# proudovyzdroj.net
KiCad netlist of a schematic drawn in EAGLE
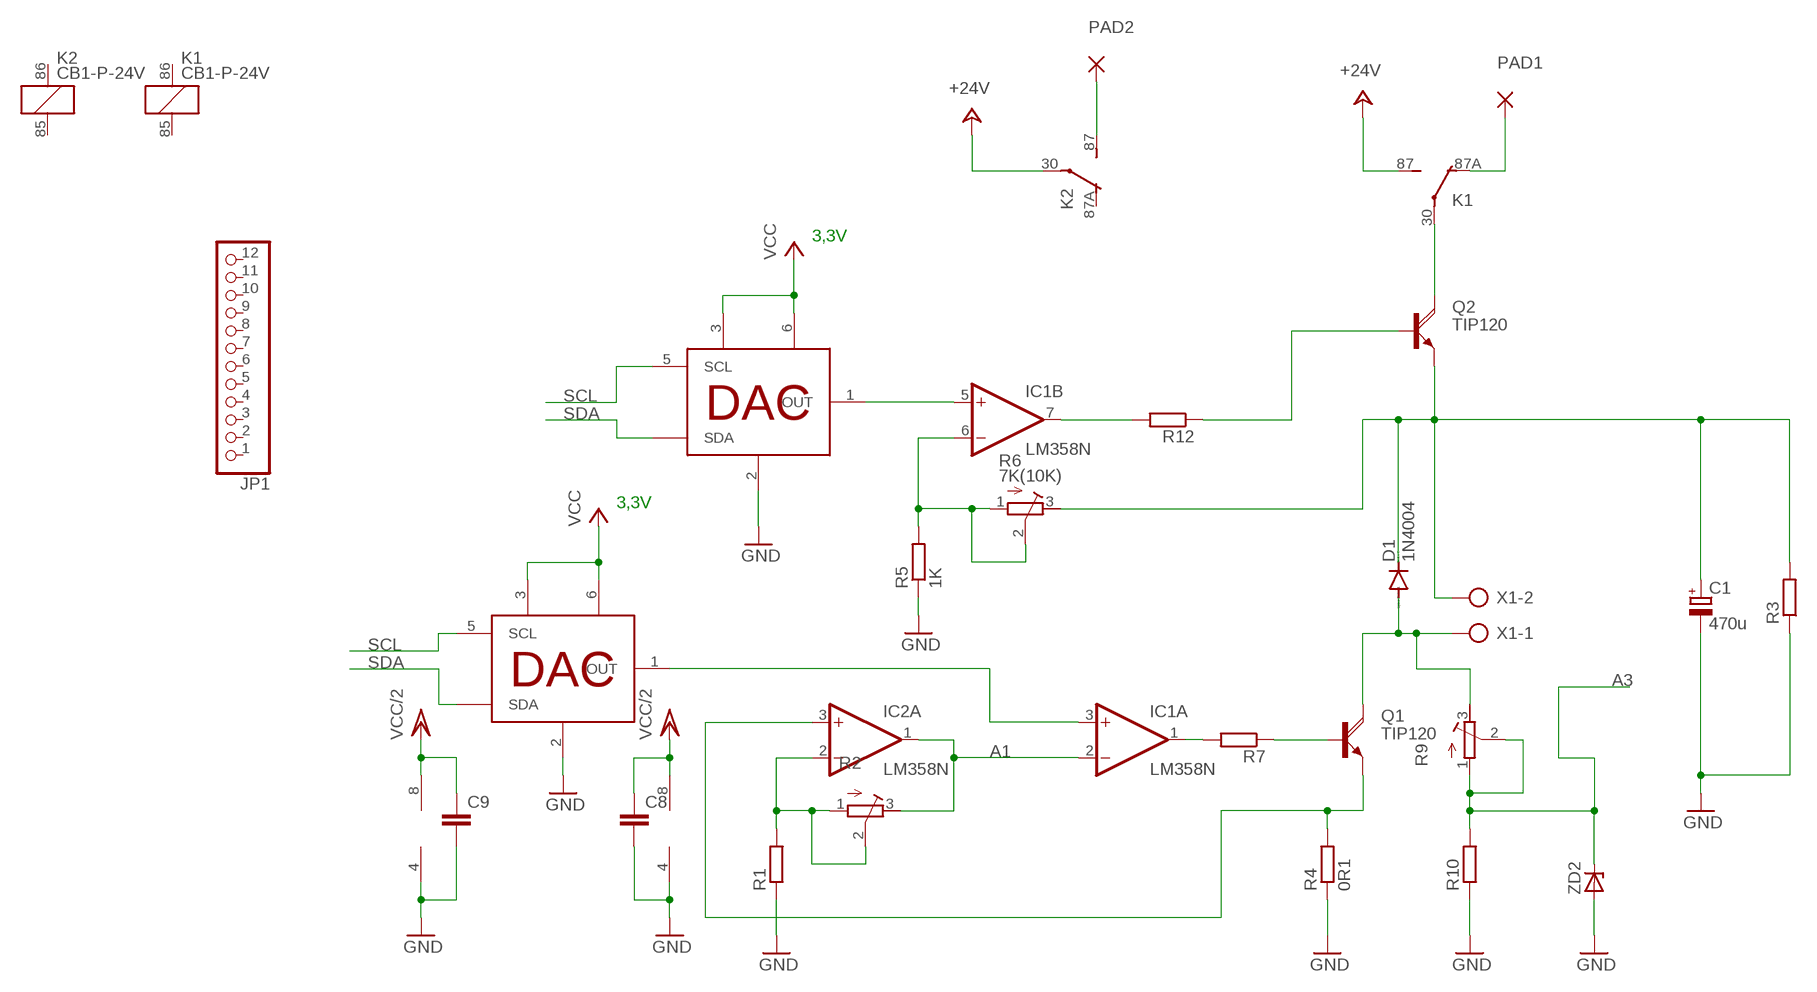
[diagram p0: schematic, sheet 1]

(export (version "E")
  (design (tool "Eeschema 10.0.6"))
  (components
    (comp (ref "C1")
      (value "470u")
      (footprint "eagle-import:E3,5-8")
      (libsource (lib "eagle-import") (part "CPOL-EUE3.5-8"))
    )
    (comp (ref "C8")
      (value "C-EUC0805")
      (footprint "eagle-import:C0805")
      (libsource (lib "eagle-import") (part "C-EUC0805"))
    )
    (comp (ref "C9")
      (value "C-EUC0805")
      (footprint "eagle-import:C0805")
      (libsource (lib "eagle-import") (part "C-EUC0805"))
    )
    (comp (ref "D1")
      (value "1N4004")
      (footprint "eagle-import:DO41-10")
      (libsource (lib "eagle-import") (part "1N4004"))
    )
    (comp (ref "IC1")
      (value "LM358N")
      (footprint "eagle-import:DIL08")
      (libsource (lib "eagle-import") (part "LM358N"))
    )
    (comp (ref "IC2")
      (value "LM358N")
      (footprint "eagle-import:DIL08")
      (libsource (lib "eagle-import") (part "LM358N"))
    )
    (comp (ref "JP1")
      (value "PINHD-1X12")
      (footprint "eagle-import:1X12")
      (libsource (lib "eagle-import") (part "PINHD-1X12"))
    )
    (comp (ref "K1")
      (value "CB1-P-24V")
      (footprint "eagle-import:CB1")
      (fields (field (name "MF") "AROMAT/ MATSUSHITA"))
      (libsource (lib "eagle-import") (part "CB1-P-24V"))
    )
    (comp (ref "K2")
      (value "CB1-P-24V")
      (footprint "eagle-import:CB1")
      (fields (field (name "MF") "AROMAT/ MATSUSHITA"))
      (libsource (lib "eagle-import") (part "CB1-P-24V"))
    )
    (comp (ref "PAD1")
      (value "3,81/1,4")
      (footprint "eagle-import:3,81_1,4")
      (libsource (lib "eagle-import") (part "3,81/1,4"))
    )
    (comp (ref "PAD2")
      (value "3,81/1,4")
      (footprint "eagle-import:3,81_1,4")
      (libsource (lib "eagle-import") (part "3,81/1,4"))
    )
    (comp (ref "Q1")
      (value "TIP120")
      (footprint "eagle-import:TO220AH")
      (libsource (lib "eagle-import") (part "TIP120"))
    )
    (comp (ref "Q2")
      (value "TIP120")
      (footprint "eagle-import:TO220AH")
      (libsource (lib "eagle-import") (part "TIP120"))
    )
    (comp (ref "R1")
      (value "R-EU_M0805")
      (footprint "eagle-import:M0805")
      (libsource (lib "eagle-import") (part "rcl_my_R-EU_M0805"))
    )
    (comp (ref "R2")
      (value "R-TRIMM3339P")
      (footprint "eagle-import:RTRIM3339P")
      (libsource (lib "eagle-import") (part "R-TRIMM3339P"))
    )
    (comp (ref "R3")
      (value "R-EU_R0805")
      (footprint "eagle-import:R0805")
      (libsource (lib "eagle-import") (part "R-EU_R0805"))
    )
    (comp (ref "R4")
      (value "0R1")
      (footprint "eagle-import:0411_15")
      (libsource (lib "eagle-import") (part "R-EU_0411/15"))
    )
    (comp (ref "R5")
      (value "1K")
      (footprint "eagle-import:R0805")
      (libsource (lib "eagle-import") (part "R-EU_R0805"))
    )
    (comp (ref "R6")
      (value "7K(10K)")
      (footprint "eagle-import:RTRIM3339P")
      (libsource (lib "eagle-import") (part "R-TRIMM3339P"))
    )
    (comp (ref "R7")
      (value "R-EU_R0805")
      (footprint "eagle-import:R0805")
      (libsource (lib "eagle-import") (part "R-EU_R0805"))
    )
    (comp (ref "R9")
      (value "R-TRIMM3339P")
      (footprint "eagle-import:RTRIM3339P")
      (libsource (lib "eagle-import") (part "R-TRIMM3339P"))
    )
    (comp (ref "R10")
      (value "R-EU_R0805")
      (footprint "eagle-import:R0805")
      (libsource (lib "eagle-import") (part "R-EU_R0805"))
    )
    (comp (ref "R12")
      (value "R-EU_R0805")
      (footprint "eagle-import:R0805")
      (libsource (lib "eagle-import") (part "R-EU_R0805"))
    )
    (comp (ref "U$5")
      (value "MCP4726")
      (footprint "eagle-import:TSOT23-6")
      (libsource (lib "eagle-import") (part "MCP4726"))
    )
    (comp (ref "U$6")
      (value "MCP4726")
      (footprint "eagle-import:TSOT23-6")
      (libsource (lib "eagle-import") (part "MCP4726"))
    )
    (comp (ref "X1")
      (value "AK500/2")
      (footprint "eagle-import:AK500_2")
      (libsource (lib "eagle-import") (part "AK500/2"))
    )
    (comp (ref "ZD2")
      (value "DIODE_ZENER5")
      (footprint "eagle-import:DO34-5")
      (libsource (lib "eagle-import") (part "DIODE_ZENER5"))
    )
  )
  (nets
    (net (code "1") (name "+24V") (class "Default")
      (node (ref "K1") (pin "87") (pinfunction "S_87") (pintype "passive"))
      (node (ref "K2") (pin "30") (pinfunction "P_30") (pintype "passive"))
    )
    (net (code "2") (name "/A1") (class "Default")
      (node (ref "IC1") (pin "2") (pinfunction "-IN_2") (pintype "input"))
      (node (ref "IC2") (pin "1") (pinfunction "OUT_1") (pintype "output"))
      (node (ref "R2") (pin "3") (pinfunction "E_3") (pintype "passive"))
    )
    (net (code "3") (name "/A3") (class "Default")
      (node (ref "R10") (pin "2") (pinfunction "2_2") (pintype "passive"))
      (node (ref "R9") (pin "1") (pinfunction "A_1") (pintype "passive"))
      (node (ref "R9") (pin "2") (pinfunction "S_2") (pintype "passive"))
      (node (ref "ZD2") (pin "C") (pinfunction "C_C") (pintype "passive"))
    )
    (net (code "4") (name "/SCL") (class "Default")
      (node (ref "U$5") (pin "5") (pinfunction "SCL_5") (pintype "bidirectional"))
      (node (ref "U$6") (pin "5") (pinfunction "SCL_5") (pintype "bidirectional"))
    )
    (net (code "5") (name "/SDA") (class "Default")
      (node (ref "U$5") (pin "4") (pinfunction "SDA_4") (pintype "bidirectional"))
      (node (ref "U$6") (pin "4") (pinfunction "SDA_4") (pintype "bidirectional"))
    )
    (net (code "6") (name "GND") (class "Default")
      (node (ref "C1") (pin "-") (pinfunction "-_-") (pintype "passive"))
      (node (ref "C8") (pin "2") (pinfunction "2_2") (pintype "passive"))
      (node (ref "C9") (pin "2") (pinfunction "2_2") (pintype "passive"))
      (node (ref "IC1") (pin "4") (pinfunction "V-_4") (pintype "power_in"))
      (node (ref "IC2") (pin "4") (pinfunction "V-_4") (pintype "power_in"))
      (node (ref "R1") (pin "1") (pinfunction "1_1") (pintype "passive"))
      (node (ref "R10") (pin "1") (pinfunction "1_1") (pintype "passive"))
      (node (ref "R3") (pin "1") (pinfunction "1_1") (pintype "passive"))
      (node (ref "R4") (pin "1") (pinfunction "1_1") (pintype "passive"))
      (node (ref "R5") (pin "1") (pinfunction "1_1") (pintype "passive"))
      (node (ref "U$5") (pin "2") (pinfunction "VSS_2") (pintype "bidirectional"))
      (node (ref "U$6") (pin "2") (pinfunction "VSS_2") (pintype "bidirectional"))
      (node (ref "ZD2") (pin "A") (pinfunction "A_A") (pintype "passive"))
    )
    (net (code "7") (name "Net-(IC1A-+IN)") (class "Default")
      (node (ref "IC1") (pin "3") (pinfunction "+IN_3") (pintype "input"))
      (node (ref "U$5") (pin "1") (pinfunction "OUT_1") (pintype "bidirectional"))
    )
    (net (code "8") (name "Net-(IC1A-OUT)") (class "Default")
      (node (ref "IC1") (pin "1") (pinfunction "OUT_1") (pintype "output"))
      (node (ref "R7") (pin "2") (pinfunction "2_2") (pintype "passive"))
    )
    (net (code "9") (name "Net-(IC1B-+IN)") (class "Default")
      (node (ref "IC1") (pin "5") (pinfunction "+IN_5") (pintype "input"))
      (node (ref "U$6") (pin "1") (pinfunction "OUT_1") (pintype "bidirectional"))
    )
    (net (code "10") (name "Net-(IC1B--IN)") (class "Default")
      (node (ref "IC1") (pin "6") (pinfunction "-IN_6") (pintype "input"))
      (node (ref "R5") (pin "2") (pinfunction "2_2") (pintype "passive"))
      (node (ref "R6") (pin "1") (pinfunction "A_1") (pintype "passive"))
      (node (ref "R6") (pin "2") (pinfunction "S_2") (pintype "passive"))
    )
    (net (code "11") (name "Net-(IC1B-OUT)") (class "Default")
      (node (ref "IC1") (pin "7") (pinfunction "OUT_7") (pintype "output"))
      (node (ref "R12") (pin "2") (pinfunction "2_2") (pintype "passive"))
    )
    (net (code "12") (name "Net-(IC2A-+IN)") (class "Default")
      (node (ref "IC2") (pin "3") (pinfunction "+IN_3") (pintype "input"))
      (node (ref "Q1") (pin "E") (pinfunction "E_E") (pintype "passive"))
      (node (ref "R4") (pin "2") (pinfunction "2_2") (pintype "passive"))
    )
    (net (code "13") (name "Net-(IC2A--IN)") (class "Default")
      (node (ref "IC2") (pin "2") (pinfunction "-IN_2") (pintype "input"))
      (node (ref "R1") (pin "2") (pinfunction "2_2") (pintype "passive"))
      (node (ref "R2") (pin "1") (pinfunction "A_1") (pintype "passive"))
      (node (ref "R2") (pin "2") (pinfunction "S_2") (pintype "passive"))
    )
    (net (code "14") (name "Net-(K1B-O)") (class "Default")
      (node (ref "K1") (pin "87A") (pinfunction "O_87A") (pintype "passive"))
      (node (ref "PAD1") (pin "1") (pinfunction "P_1") (pintype "passive"))
    )
    (net (code "15") (name "Net-(K1B-P)") (class "Default")
      (node (ref "K1") (pin "30") (pinfunction "P_30") (pintype "passive"))
      (node (ref "Q2") (pin "C") (pinfunction "C_C") (pintype "passive"))
    )
    (net (code "16") (name "Net-(K2B-S)") (class "Default")
      (node (ref "K2") (pin "87") (pinfunction "S_87") (pintype "passive"))
      (node (ref "PAD2") (pin "1") (pinfunction "P_1") (pintype "passive"))
    )
    (net (code "17") (name "Net-(Q1-PadB)") (class "Default")
      (node (ref "Q1") (pin "B") (pinfunction "B_B") (pintype "passive"))
      (node (ref "R7") (pin "1") (pinfunction "1_1") (pintype "passive"))
    )
    (net (code "18") (name "Net-(Q2-PadB)") (class "Default")
      (node (ref "Q2") (pin "B") (pinfunction "B_B") (pintype "passive"))
      (node (ref "R12") (pin "1") (pinfunction "1_1") (pintype "passive"))
    )
    (net (code "19") (name "Net-(R6-E)") (class "Default")
      (node (ref "C1") (pin "+") (pinfunction "+_+") (pintype "passive"))
      (node (ref "D1") (pin "C") (pinfunction "C_C") (pintype "passive"))
      (node (ref "Q2") (pin "E") (pinfunction "E_E") (pintype "passive"))
      (node (ref "R3") (pin "2") (pinfunction "2_2") (pintype "passive"))
      (node (ref "R6") (pin "3") (pinfunction "E_3") (pintype "passive"))
      (node (ref "X1") (pin "2") (pinfunction "KL_2") (pintype "passive"))
    )
    (net (code "20") (name "Net-(R9-E)") (class "Default")
      (node (ref "D1") (pin "A") (pinfunction "A_A") (pintype "passive"))
      (node (ref "Q1") (pin "C") (pinfunction "C_C") (pintype "passive"))
      (node (ref "R9") (pin "3") (pinfunction "E_3") (pintype "passive"))
      (node (ref "X1") (pin "1") (pinfunction "KL_1") (pintype "passive"))
    )
    (net (code "21") (name "VCC") (class "Default")
      (node (ref "U$5") (pin "3") (pinfunction "VDD_3") (pintype "bidirectional"))
      (node (ref "U$5") (pin "6") (pinfunction "VREF_6") (pintype "bidirectional"))
      (node (ref "U$6") (pin "3") (pinfunction "VDD_3") (pintype "bidirectional"))
      (node (ref "U$6") (pin "6") (pinfunction "VREF_6") (pintype "bidirectional"))
    )
    (net (code "22") (name "VCC{slash}2") (class "Default")
      (node (ref "C8") (pin "1") (pinfunction "1_1") (pintype "passive"))
      (node (ref "C9") (pin "1") (pinfunction "1_1") (pintype "passive"))
      (node (ref "IC1") (pin "8") (pinfunction "V+_8") (pintype "power_in"))
      (node (ref "IC2") (pin "8") (pinfunction "V+_8") (pintype "power_in"))
    )
    (net (code "23") (name "unconnected-(JP1-Pad1)") (class "Default")
      (node (ref "JP1") (pin "1") (pinfunction "1_1") (pintype "passive"))
    )
    (net (code "24") (name "unconnected-(JP1-Pad2)") (class "Default")
      (node (ref "JP1") (pin "2") (pinfunction "2_2") (pintype "passive"))
    )
    (net (code "25") (name "unconnected-(JP1-Pad3)") (class "Default")
      (node (ref "JP1") (pin "3") (pinfunction "3_3") (pintype "passive"))
    )
    (net (code "26") (name "unconnected-(JP1-Pad4)") (class "Default")
      (node (ref "JP1") (pin "4") (pinfunction "4_4") (pintype "passive"))
    )
    (net (code "27") (name "unconnected-(JP1-Pad5)") (class "Default")
      (node (ref "JP1") (pin "5") (pinfunction "5_5") (pintype "passive"))
    )
    (net (code "28") (name "unconnected-(JP1-Pad6)") (class "Default")
      (node (ref "JP1") (pin "6") (pinfunction "6_6") (pintype "passive"))
    )
    (net (code "29") (name "unconnected-(JP1-Pad7)") (class "Default")
      (node (ref "JP1") (pin "7") (pinfunction "7_7") (pintype "passive"))
    )
    (net (code "30") (name "unconnected-(JP1-Pad8)") (class "Default")
      (node (ref "JP1") (pin "8") (pinfunction "8_8") (pintype "passive"))
    )
    (net (code "31") (name "unconnected-(JP1-Pad9)") (class "Default")
      (node (ref "JP1") (pin "9") (pinfunction "9_9") (pintype "passive"))
    )
    (net (code "32") (name "unconnected-(JP1-Pad10)") (class "Default")
      (node (ref "JP1") (pin "10") (pinfunction "10_10") (pintype "passive"))
    )
    (net (code "33") (name "unconnected-(JP1-Pad11)") (class "Default")
      (node (ref "JP1") (pin "11") (pinfunction "11_11") (pintype "passive"))
    )
    (net (code "34") (name "unconnected-(JP1-Pad12)") (class "Default")
      (node (ref "JP1") (pin "12") (pinfunction "12_12") (pintype "passive"))
    )
    (net (code "35") (name "unconnected-(K1A-1-Pad86)") (class "Default")
      (node (ref "K1") (pin "86") (pinfunction "1_86") (pintype "passive"))
    )
    (net (code "36") (name "unconnected-(K1A-2-Pad85)") (class "Default")
      (node (ref "K1") (pin "85") (pinfunction "2_85") (pintype "passive"))
    )
    (net (code "37") (name "unconnected-(K2A-1-Pad86)") (class "Default")
      (node (ref "K2") (pin "86") (pinfunction "1_86") (pintype "passive"))
    )
    (net (code "38") (name "unconnected-(K2A-2-Pad85)") (class "Default")
      (node (ref "K2") (pin "85") (pinfunction "2_85") (pintype "passive"))
    )
    (net (code "39") (name "unconnected-(K2B-O-Pad87A)") (class "Default")
      (node (ref "K2") (pin "87A") (pinfunction "O_87A") (pintype "passive"))
    )
  )
)
